# MIDI_Schematic.net
KiCad netlist of a schematic drawn in Altium Designer
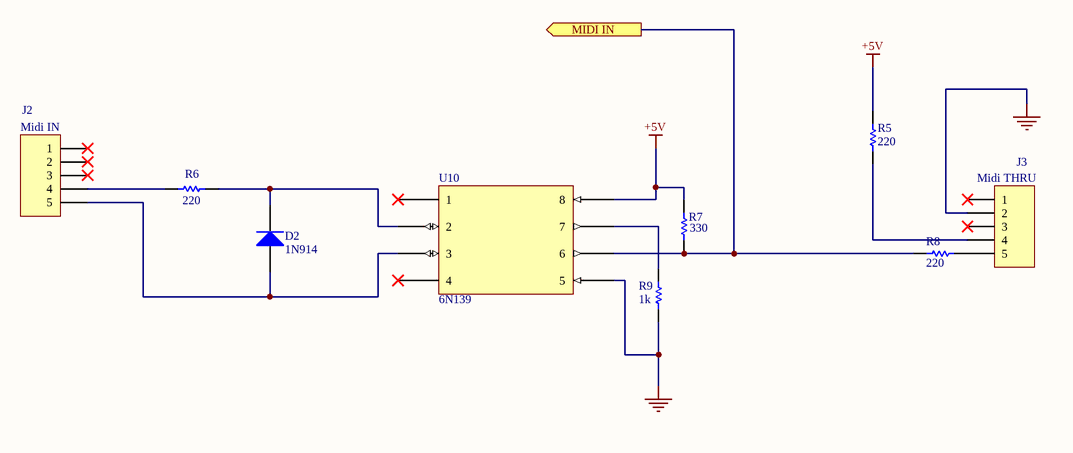
[diagram p0: MIDI.Schematic.SchDoc]

(export (version "E")
  (design (tool "Eeschema 10.0.6"))
  (components
    (comp (ref "D2")
      (value "1N914")
      (footprint "1N914")
      (description "Default Diode")
      (fields (field (name "PUBLISHER") "Altium Limited"))
      (libsource (lib "Miscellaneous Devices") (part "Diode"))
    )
    (comp (ref "J2")
      (value "Midi IN")
      (footprint "SOCKET MIDI")
      (description "DIN 5 Pins")
      (fields (field (name "PUBLISHER") "Altium Limited"))
      (libsource (lib "Miscellaneous Connectors") (part "Header 5"))
    )
    (comp (ref "J3")
      (value "Midi THRU")
      (footprint "SOCKET MIDI")
      (description "DIN 5 Pins")
      (fields (field (name "PUBLISHER") "Altium Limited"))
      (libsource (lib "") (part "Header 5_1"))
    )
    (comp (ref "R5")
      (value "220")
      (footprint "CAPC1608N")
      (description "Resistor")
      (fields (field (name "Comment") "Res1") (field (name "PUBLISHER") "Altium Limited"))
      (libsource (lib "Miscellaneous Devices") (part "Res1"))
    )
    (comp (ref "R6")
      (value "220")
      (footprint "CAPC1608N")
      (description "Resistor")
      (fields (field (name "Comment") "Res1") (field (name "PUBLISHER") "Altium Limited"))
      (libsource (lib "Miscellaneous Devices") (part "Res1"))
    )
    (comp (ref "R7")
      (value "330")
      (footprint "CAPC1608N")
      (description "Resistor")
      (fields (field (name "PUBLISHER") "Altium Limited"))
      (libsource (lib "Miscellaneous Devices") (part "Res1"))
    )
    (comp (ref "R8")
      (value "220")
      (footprint "CAPC1608N")
      (description "Resistor")
      (fields (field (name "Comment") "Res1") (field (name "PUBLISHER") "Altium Limited"))
      (libsource (lib "Miscellaneous Devices") (part "Res1"))
    )
    (comp (ref "R9")
      (value "1k")
      (footprint "CAPC1608N")
      (description "Resistor")
      (fields (field (name "PUBLISHER") "Altium Limited"))
      (libsource (lib "Miscellaneous Devices") (part "Res1"))
    )
    (comp (ref "U10")
      (value "6N139")
      (footprint "6N139")
      (libsource (lib "SynthyTwo.Components") (part "Optocoupleur"))
    )
  )
  (nets
    (net (code "1") (name "+5V") (class "Default")
      (node (ref "R5") (pin "2") (pinfunction "2_2") (pintype "passive"))
      (node (ref "R7") (pin "2") (pinfunction "2_2") (pintype "passive"))
      (node (ref "U10") (pin "8") (pinfunction "8_8") (pintype "input"))
    )
    (net (code "2") (name "/MIDI IN") (class "Default")
      (node (ref "R7") (pin "1") (pinfunction "1_1") (pintype "passive"))
      (node (ref "R8") (pin "2") (pinfunction "2_2") (pintype "passive"))
      (node (ref "U10") (pin "6") (pinfunction "6_6") (pintype "output"))
    )
    (net (code "3") (name "GND") (class "Default")
      (node (ref "J3") (pin "2") (pinfunction "2_2") (pintype "passive"))
      (node (ref "R9") (pin "1") (pinfunction "1_1") (pintype "passive"))
      (node (ref "U10") (pin "5") (pinfunction "5_5") (pintype "input"))
    )
    (net (code "4") (name "Net-(D2-A)") (class "Default")
      (node (ref "D2") (pin "1") (pinfunction "A_1") (pintype "passive"))
      (node (ref "J2") (pin "5") (pinfunction "5_5") (pintype "passive"))
      (node (ref "U10") (pin "3") (pinfunction "3_3") (pintype "bidirectional"))
    )
    (net (code "5") (name "Net-(D2-K)") (class "Default")
      (node (ref "D2") (pin "2") (pinfunction "K_2") (pintype "passive"))
      (node (ref "R6") (pin "2") (pinfunction "2_2") (pintype "passive"))
      (node (ref "U10") (pin "2") (pinfunction "2_2") (pintype "bidirectional"))
    )
    (net (code "6") (name "Net-(J2-Pad4)") (class "Default")
      (node (ref "J2") (pin "4") (pinfunction "4_4") (pintype "passive"))
      (node (ref "R6") (pin "1") (pinfunction "1_1") (pintype "passive"))
    )
    (net (code "7") (name "Net-(J3-Pad4)") (class "Default")
      (node (ref "J3") (pin "4") (pinfunction "4_4") (pintype "passive"))
      (node (ref "R5") (pin "1") (pinfunction "1_1") (pintype "passive"))
    )
    (net (code "8") (name "Net-(J3-Pad5)") (class "Default")
      (node (ref "J3") (pin "5") (pinfunction "5_5") (pintype "passive"))
      (node (ref "R8") (pin "1") (pinfunction "1_1") (pintype "passive"))
    )
    (net (code "9") (name "Net-(R9-Pad2)") (class "Default")
      (node (ref "R9") (pin "2") (pinfunction "2_2") (pintype "passive"))
      (node (ref "U10") (pin "7") (pinfunction "7_7") (pintype "output"))
    )
    (net (code "10") (name "unconnected-(J2-Pad1)") (class "Default")
      (node (ref "J2") (pin "1") (pinfunction "1_1") (pintype "passive+no_connect"))
    )
    (net (code "11") (name "unconnected-(J2-Pad2)") (class "Default")
      (node (ref "J2") (pin "2") (pinfunction "2_2") (pintype "passive+no_connect"))
    )
    (net (code "12") (name "unconnected-(J2-Pad3)") (class "Default")
      (node (ref "J2") (pin "3") (pinfunction "3_3") (pintype "passive+no_connect"))
    )
    (net (code "13") (name "unconnected-(J3-Pad1)") (class "Default")
      (node (ref "J3") (pin "1") (pinfunction "1_1") (pintype "passive+no_connect"))
    )
    (net (code "14") (name "unconnected-(J3-Pad3)") (class "Default")
      (node (ref "J3") (pin "3") (pinfunction "3_3") (pintype "passive+no_connect"))
    )
    (net (code "15") (name "unconnected-(U10-Pad1)") (class "Default")
      (node (ref "U10") (pin "1") (pinfunction "1_1") (pintype "passive+no_connect"))
    )
    (net (code "16") (name "unconnected-(U10-Pad4)") (class "Default")
      (node (ref "U10") (pin "4") (pinfunction "4_4") (pintype "passive+no_connect"))
    )
  )
)
